# Flash_Memory.net
KiCad netlist of a schematic drawn in Altium Designer
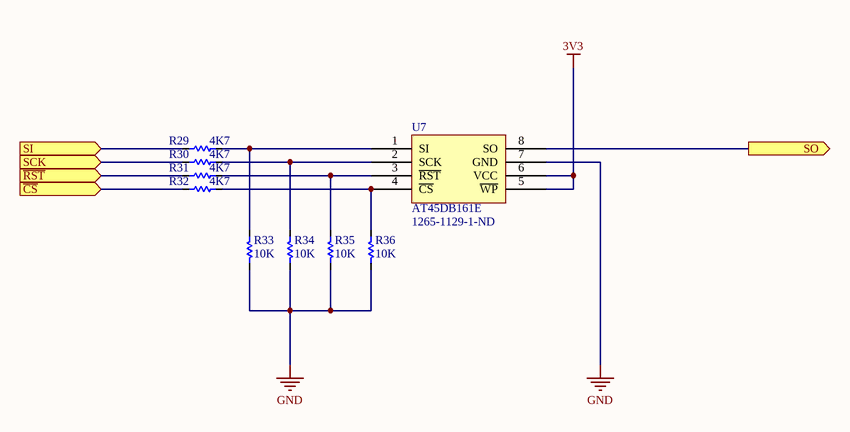
[diagram p0: Flash_Memory.SchDoc]

(export (version "E")
  (design (tool "Eeschema 10.0.6"))
  (components
    (comp (ref "R29")
      (value "4K7")
      (footprint "R0603(1608)")
      (description "Resistor")
      (libsource (lib "ali_lib") (part "R"))
    )
    (comp (ref "R30")
      (value "4K7")
      (footprint "R0603(1608)")
      (description "Resistor")
      (libsource (lib "ali_lib") (part "R"))
    )
    (comp (ref "R31")
      (value "4K7")
      (footprint "R0603(1608)")
      (description "Resistor")
      (libsource (lib "ali_lib") (part "R"))
    )
    (comp (ref "R32")
      (value "4K7")
      (footprint "R0603(1608)")
      (description "Resistor")
      (libsource (lib "ali_lib") (part "R"))
    )
    (comp (ref "R33")
      (value "10K")
      (footprint "R0603(1608)")
      (description "Resistor")
      (libsource (lib "ali_lib") (part "R"))
    )
    (comp (ref "R34")
      (value "10K")
      (footprint "R0603(1608)")
      (description "Resistor")
      (libsource (lib "ali_lib") (part "R"))
    )
    (comp (ref "R35")
      (value "10K")
      (footprint "R0603(1608)")
      (description "Resistor")
      (libsource (lib "ali_lib") (part "R"))
    )
    (comp (ref "R36")
      (value "10K")
      (footprint "R0603(1608)")
      (description "Resistor")
      (libsource (lib "ali_lib") (part "R"))
    )
    (comp (ref "U7")
      (value "AT45DB161E")
      (footprint "8-UDFN 5x6")
      (description "SPI Flash Memory")
      (fields
        (field (name "MANUFACTURER") "Adesto Technologies")
        (field (name "MANUFACTURER PART NUMBER") "AT45DB161E-MHD2B-T")
        (field (name "SUPPLIER PART NUMBER 1") "1265-1129-1-ND")
      )
      (libsource (lib "Flight_Controller") (part "AT45DB161E"))
    )
  )
  (nets
    (net (code "1") (name "/SCK") (class "Default")
      (node (ref "R30") (pin "2") (pinfunction "2_2") (pintype "passive"))
    )
    (net (code "2") (name "/SI") (class "Default")
      (node (ref "R29") (pin "2") (pinfunction "2_2") (pintype "passive"))
    )
    (net (code "3") (name "/SO") (class "Default")
      (node (ref "U7") (pin "8") (pinfunction "SO_8") (pintype "passive"))
    )
    (net (code "4") (name "/~{CS}") (class "Default")
      (node (ref "R32") (pin "2") (pinfunction "2_2") (pintype "passive"))
    )
    (net (code "5") (name "/~{RST}") (class "Default")
      (node (ref "R31") (pin "2") (pinfunction "2_2") (pintype "passive"))
    )
    (net (code "6") (name "3V3") (class "Default")
      (node (ref "U7") (pin "5") (pinfunction "~{WP}_5") (pintype "passive"))
      (node (ref "U7") (pin "6") (pinfunction "VCC_6") (pintype "passive"))
    )
    (net (code "7") (name "GND") (class "Default")
      (node (ref "R33") (pin "2") (pinfunction "2_2") (pintype "passive"))
      (node (ref "R34") (pin "2") (pinfunction "2_2") (pintype "passive"))
      (node (ref "R35") (pin "2") (pinfunction "2_2") (pintype "passive"))
      (node (ref "R36") (pin "2") (pinfunction "2_2") (pintype "passive"))
      (node (ref "U7") (pin "7") (pinfunction "GND_7") (pintype "passive"))
    )
    (net (code "8") (name "Net-(U7-SCK)") (class "Default")
      (node (ref "R30") (pin "1") (pinfunction "1_1") (pintype "passive"))
      (node (ref "R34") (pin "1") (pinfunction "1_1") (pintype "passive"))
      (node (ref "U7") (pin "2") (pinfunction "SCK_2") (pintype "passive"))
    )
    (net (code "9") (name "Net-(U7-SI)") (class "Default")
      (node (ref "R29") (pin "1") (pinfunction "1_1") (pintype "passive"))
      (node (ref "R33") (pin "1") (pinfunction "1_1") (pintype "passive"))
      (node (ref "U7") (pin "1") (pinfunction "SI_1") (pintype "passive"))
    )
    (net (code "10") (name "Net-(U7-~{CS})") (class "Default")
      (node (ref "R32") (pin "1") (pinfunction "1_1") (pintype "passive"))
      (node (ref "R36") (pin "1") (pinfunction "1_1") (pintype "passive"))
      (node (ref "U7") (pin "4") (pinfunction "~{CS}_4") (pintype "passive"))
    )
    (net (code "11") (name "Net-(U7-~{RST})") (class "Default")
      (node (ref "R31") (pin "1") (pinfunction "1_1") (pintype "passive"))
      (node (ref "R35") (pin "1") (pinfunction "1_1") (pintype "passive"))
      (node (ref "U7") (pin "3") (pinfunction "~{RST}_3") (pintype "passive"))
    )
  )
)
